# 4a_-_Latching_AMS.net
KiCad netlist of a schematic drawn in Altium Designer
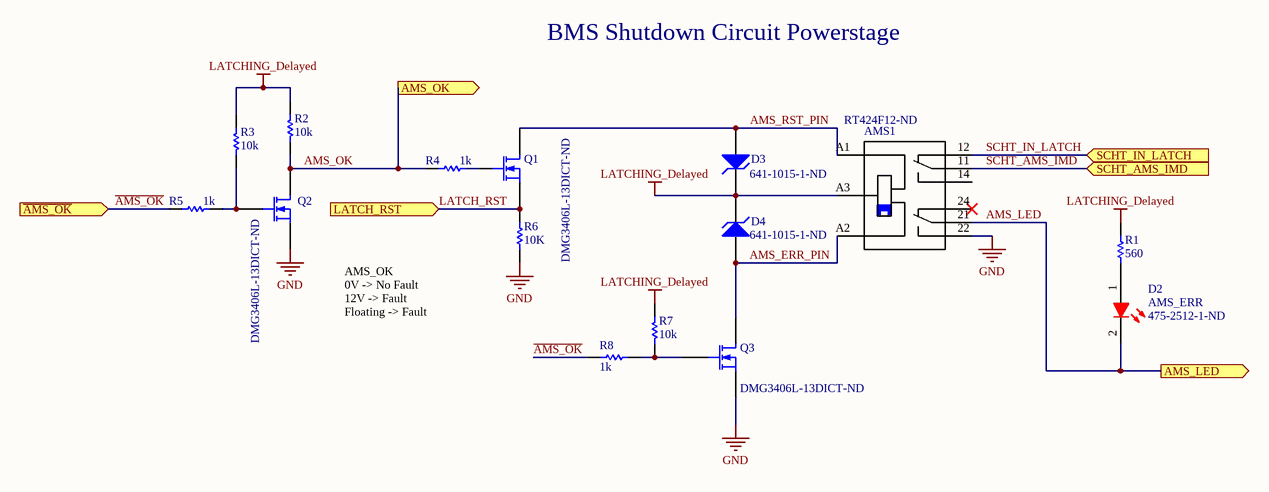
[diagram p0: 4a - Latching AMS.SchDoc]

(export (version "E")
  (design (tool "Eeschema 10.0.6"))
  (components
    (comp (ref "AMS1")
      (value "5-1393243-4")
      (footprint "TE_5-1393243-4")
      (description "Electromechanical Relay 12VDC 240Ohm 15A DPDT __ 29mm 12.7mm 15.7mm__ THT Power Relay")
      (fields (field (name "MF") "TE Connectivity") (field (name "SUPPLIER PART NUMBER 1") "RT424F12-ND"))
      (libsource (lib "5-1393243-4") (part "5-1393243-4"))
    )
    (comp (ref "D2")
      (value "AMS_ERR")
      (footprint "TOSH-0603LED_RED_V")
      (description "LED, Red 0603 (1608) 63mCd")
      (fields
        (field (name "MANUFACTURER") "Toshiba")
        (field (name "PARTNUMBER") "TLSU1008A(T04)")
        (field (name "SUPPLIER PART NUMBER 1") "475-2512-1-ND")
      )
      (libsource (lib "Altium Content Vault") (part "CMP-0444-00001-1"))
    )
    (comp (ref "D3")
      (value "D Zener")
      (footprint "DO214AC")
      (description "Zener Diode")
      (fields
        (field (name "SUPPLIER PART NUMBER 1") "641-1015-1-ND")
        (field (name "PUBLISHER") "Altium Limited")
      )
      (libsource (lib "Miscellaneous Devices") (part "D Zener"))
    )
    (comp (ref "D4")
      (value "D Zener")
      (footprint "DO214AC")
      (description "Zener Diode")
      (fields
        (field (name "SUPPLIER PART NUMBER 1") "641-1015-1-ND")
        (field (name "PUBLISHER") "Altium Limited")
      )
      (libsource (lib "Miscellaneous Devices") (part "D Zener"))
    )
    (comp (ref "Q1")
      (value "~")
      (footprint "SOT-23_N")
      (description "N-Channel MOSFET")
      (fields
        (field (name "MANUFACTURER") "Infineon Technologies")
        (field (name "SUPPLIER PART NUMBER 1") "DMG3406L-13DICT-ND")
        (field (name "PUBLISHER") "Altium Limited")
      )
      (libsource (lib "Miscellaneous Devices") (part "MOSFET-N"))
    )
    (comp (ref "Q2")
      (value "~")
      (footprint "SOT-23_N")
      (description "N-Channel MOSFET")
      (fields
        (field (name "MANUFACTURER") "Infineon Technologies")
        (field (name "SUPPLIER PART NUMBER 1") "DMG3406L-13DICT-ND")
        (field (name "PUBLISHER") "Altium Limited")
      )
      (libsource (lib "Miscellaneous Devices") (part "MOSFET-N"))
    )
    (comp (ref "Q3")
      (value "~")
      (footprint "SOT-23_N")
      (description "N-Channel MOSFET")
      (fields
        (field (name "MANUFACTURER") "Infineon Technologies")
        (field (name "SUPPLIER PART NUMBER 1") "DMG3406L-13DICT-ND")
        (field (name "PUBLISHER") "Altium Limited")
      )
      (libsource (lib "Miscellaneous Devices") (part "MOSFET-N"))
    )
    (comp (ref "R1")
      (value "560")
      (footprint "RESC0603(1608)_L")
      (description "0603 (1608 Metric) Chip Resistor")
      (libsource (lib "Altium Content Vault") (part "RES_3"))
    )
    (comp (ref "R2")
      (value "RHM1.0KDCT-ND")
      (footprint "1608[0603]")
      (description "RES SMD 1.0K OHM 5% 1/4W 0603")
      (fields
        (field (name "MANUFACTURER") "Rohm Semiconductor")
        (field (name "MANUFACTURER PART NUMBER") "ESR03EZPJ102")
        (field (name "RESISTANCE (OHMS)") "10k")
      )
      (libsource (lib "Miscellaneous Devices") (part "Res1"))
    )
    (comp (ref "R3")
      (value "RHM1.0KDCT-ND")
      (footprint "1608[0603]")
      (description "RES SMD 1.0K OHM 5% 1/4W 0603")
      (fields
        (field (name "MANUFACTURER") "Rohm Semiconductor")
        (field (name "MANUFACTURER PART NUMBER") "ESR03EZPJ102")
        (field (name "RESISTANCE (OHMS)") "10k")
      )
      (libsource (lib "Miscellaneous Devices") (part "Res1"))
    )
    (comp (ref "R4")
      (value "1k")
      (footprint "1608[0603]")
      (description "RES SMD 100 OHM 5% 1/4W 0603")
      (fields
        (field (name "MANUFACTURER") "Rohm Semiconductor")
        (field (name "MANUFACTURER PART NUMBER") "ESR03EZPJ101")
        (field (name "PUBLISHER") "Altium Limited")
      )
      (libsource (lib "Miscellaneous Devices") (part "Res1"))
    )
    (comp (ref "R5")
      (value "1k")
      (footprint "1608[0603]")
      (description "RES SMD 100 OHM 5% 1/4W 0603")
      (fields
        (field (name "MANUFACTURER") "Rohm Semiconductor")
        (field (name "MANUFACTURER PART NUMBER") "ESR03EZPJ101")
        (field (name "PUBLISHER") "Altium Limited")
      )
      (libsource (lib "Miscellaneous Devices") (part "Res1"))
    )
    (comp (ref "R6")
      (value "10K")
      (footprint "1608[0603]")
      (description "RES SMD 10K OHM 5% 1/4W 0603")
      (fields
        (field (name "MANUFACTURER") "Rohm Semiconductor")
        (field (name "MANUFACTURER PART NUMBER") "ESR03EZPJ103")
        (field (name "PUBLISHER") "Altium Limited")
      )
      (libsource (lib "Miscellaneous Devices") (part "Res1"))
    )
    (comp (ref "R7")
      (value "RHM1.0KDCT-ND")
      (footprint "1608[0603]")
      (description "RES SMD 1.0K OHM 5% 1/4W 0603")
      (fields
        (field (name "MANUFACTURER") "Rohm Semiconductor")
        (field (name "MANUFACTURER PART NUMBER") "ESR03EZPJ102")
        (field (name "RESISTANCE (OHMS)") "10k")
      )
      (libsource (lib "Miscellaneous Devices") (part "Res1"))
    )
    (comp (ref "R8")
      (value "1k")
      (footprint "1608[0603]")
      (description "Resistor")
      (fields
        (field (name "MANUFACTURER") "Panasonic Electronic Components")
        (field (name "MANUFACTURER PART NUMBER") "ERJ-3EKF60R4V")
        (field (name "PUBLISHER") "Altium Limited")
      )
      (libsource (lib "Miscellaneous Devices") (part "Res1"))
    )
  )
  (nets
    (net (code "1") (name "/AMS_ERR_PIN") (class "Default")
      (node (ref "AMS1") (pin "A2") (pinfunction "A2_A2") (pintype "passive"))
      (node (ref "D4") (pin "1") (pinfunction "A_1") (pintype "passive"))
      (node (ref "Q3") (pin "3") (pinfunction "D_3") (pintype "passive"))
    )
    (net (code "2") (name "/AMS_LED") (class "Default")
      (node (ref "AMS1") (pin "21") (pinfunction "21_21") (pintype "passive"))
      (node (ref "D2") (pin "2") (pinfunction "K_2") (pintype "passive"))
    )
    (net (code "3") (name "/AMS_OK") (class "Default")
      (node (ref "Q2") (pin "3") (pinfunction "D_3") (pintype "passive"))
      (node (ref "R2") (pin "2") (pinfunction "2_2") (pintype "passive"))
      (node (ref "R4") (pin "1") (pinfunction "1_1") (pintype "passive"))
    )
    (net (code "4") (name "/AMS_RST_PIN") (class "Default")
      (node (ref "AMS1") (pin "A1") (pinfunction "A1_A1") (pintype "passive"))
      (node (ref "D3") (pin "1") (pinfunction "A_1") (pintype "passive"))
      (node (ref "Q1") (pin "3") (pinfunction "D_3") (pintype "passive"))
    )
    (net (code "5") (name "/LATCH_RST") (class "Default")
      (node (ref "Q1") (pin "2") (pinfunction "S_2") (pintype "passive"))
      (node (ref "R6") (pin "2") (pinfunction "2_2") (pintype "passive"))
    )
    (net (code "6") (name "/SCHT_AMS_IMD") (class "Default")
      (node (ref "AMS1") (pin "11") (pinfunction "11_11") (pintype "passive"))
    )
    (net (code "7") (name "/SCHT_IN_LATCH") (class "Default")
      (node (ref "AMS1") (pin "12") (pinfunction "12_12") (pintype "passive"))
    )
    (net (code "8") (name "/~{AMS_OK}") (class "Default")
      (node (ref "R5") (pin "1") (pinfunction "1_1") (pintype "passive"))
      (node (ref "R8") (pin "1") (pinfunction "1_1") (pintype "passive"))
    )
    (net (code "9") (name "GND") (class "Default")
      (node (ref "AMS1") (pin "22") (pinfunction "22_22") (pintype "passive"))
      (node (ref "Q2") (pin "2") (pinfunction "S_2") (pintype "passive"))
      (node (ref "Q3") (pin "2") (pinfunction "S_2") (pintype "passive"))
      (node (ref "R6") (pin "1") (pinfunction "1_1") (pintype "passive"))
    )
    (net (code "10") (name "LATCHING_Delayed") (class "Default")
      (node (ref "AMS1") (pin "A3") (pinfunction "A3_A3") (pintype "passive"))
      (node (ref "D3") (pin "2") (pinfunction "K_2") (pintype "passive"))
      (node (ref "D4") (pin "2") (pinfunction "K_2") (pintype "passive"))
      (node (ref "R1") (pin "2") (pinfunction "2_2") (pintype "passive"))
      (node (ref "R2") (pin "1") (pinfunction "1_1") (pintype "passive"))
      (node (ref "R3") (pin "1") (pinfunction "1_1") (pintype "passive"))
      (node (ref "R7") (pin "1") (pinfunction "1_1") (pintype "passive"))
    )
    (net (code "11") (name "Net-(D2-A)") (class "Default")
      (node (ref "D2") (pin "1") (pinfunction "A_1") (pintype "passive"))
      (node (ref "R1") (pin "1") (pinfunction "1_1") (pintype "passive"))
    )
    (net (code "12") (name "Net-(Q1-G)") (class "Default")
      (node (ref "Q1") (pin "1") (pinfunction "G_1") (pintype "passive"))
      (node (ref "R4") (pin "2") (pinfunction "2_2") (pintype "passive"))
    )
    (net (code "13") (name "Net-(Q2-G)") (class "Default")
      (node (ref "Q2") (pin "1") (pinfunction "G_1") (pintype "passive"))
      (node (ref "R3") (pin "2") (pinfunction "2_2") (pintype "passive"))
      (node (ref "R5") (pin "2") (pinfunction "2_2") (pintype "passive"))
    )
    (net (code "14") (name "Net-(Q3-G)") (class "Default")
      (node (ref "Q3") (pin "1") (pinfunction "G_1") (pintype "passive"))
      (node (ref "R7") (pin "2") (pinfunction "2_2") (pintype "passive"))
      (node (ref "R8") (pin "2") (pinfunction "2_2") (pintype "passive"))
    )
    (net (code "15") (name "unconnected-(AMS1-Pad14)") (class "Default")
      (node (ref "AMS1") (pin "14") (pinfunction "14_14") (pintype "passive"))
    )
    (net (code "16") (name "unconnected-(AMS1-Pad24)") (class "Default")
      (node (ref "AMS1") (pin "24") (pinfunction "24_24") (pintype "passive+no_connect"))
    )
  )
)
